# makey_makey.net
KiCad netlist of a schematic drawn in EAGLE
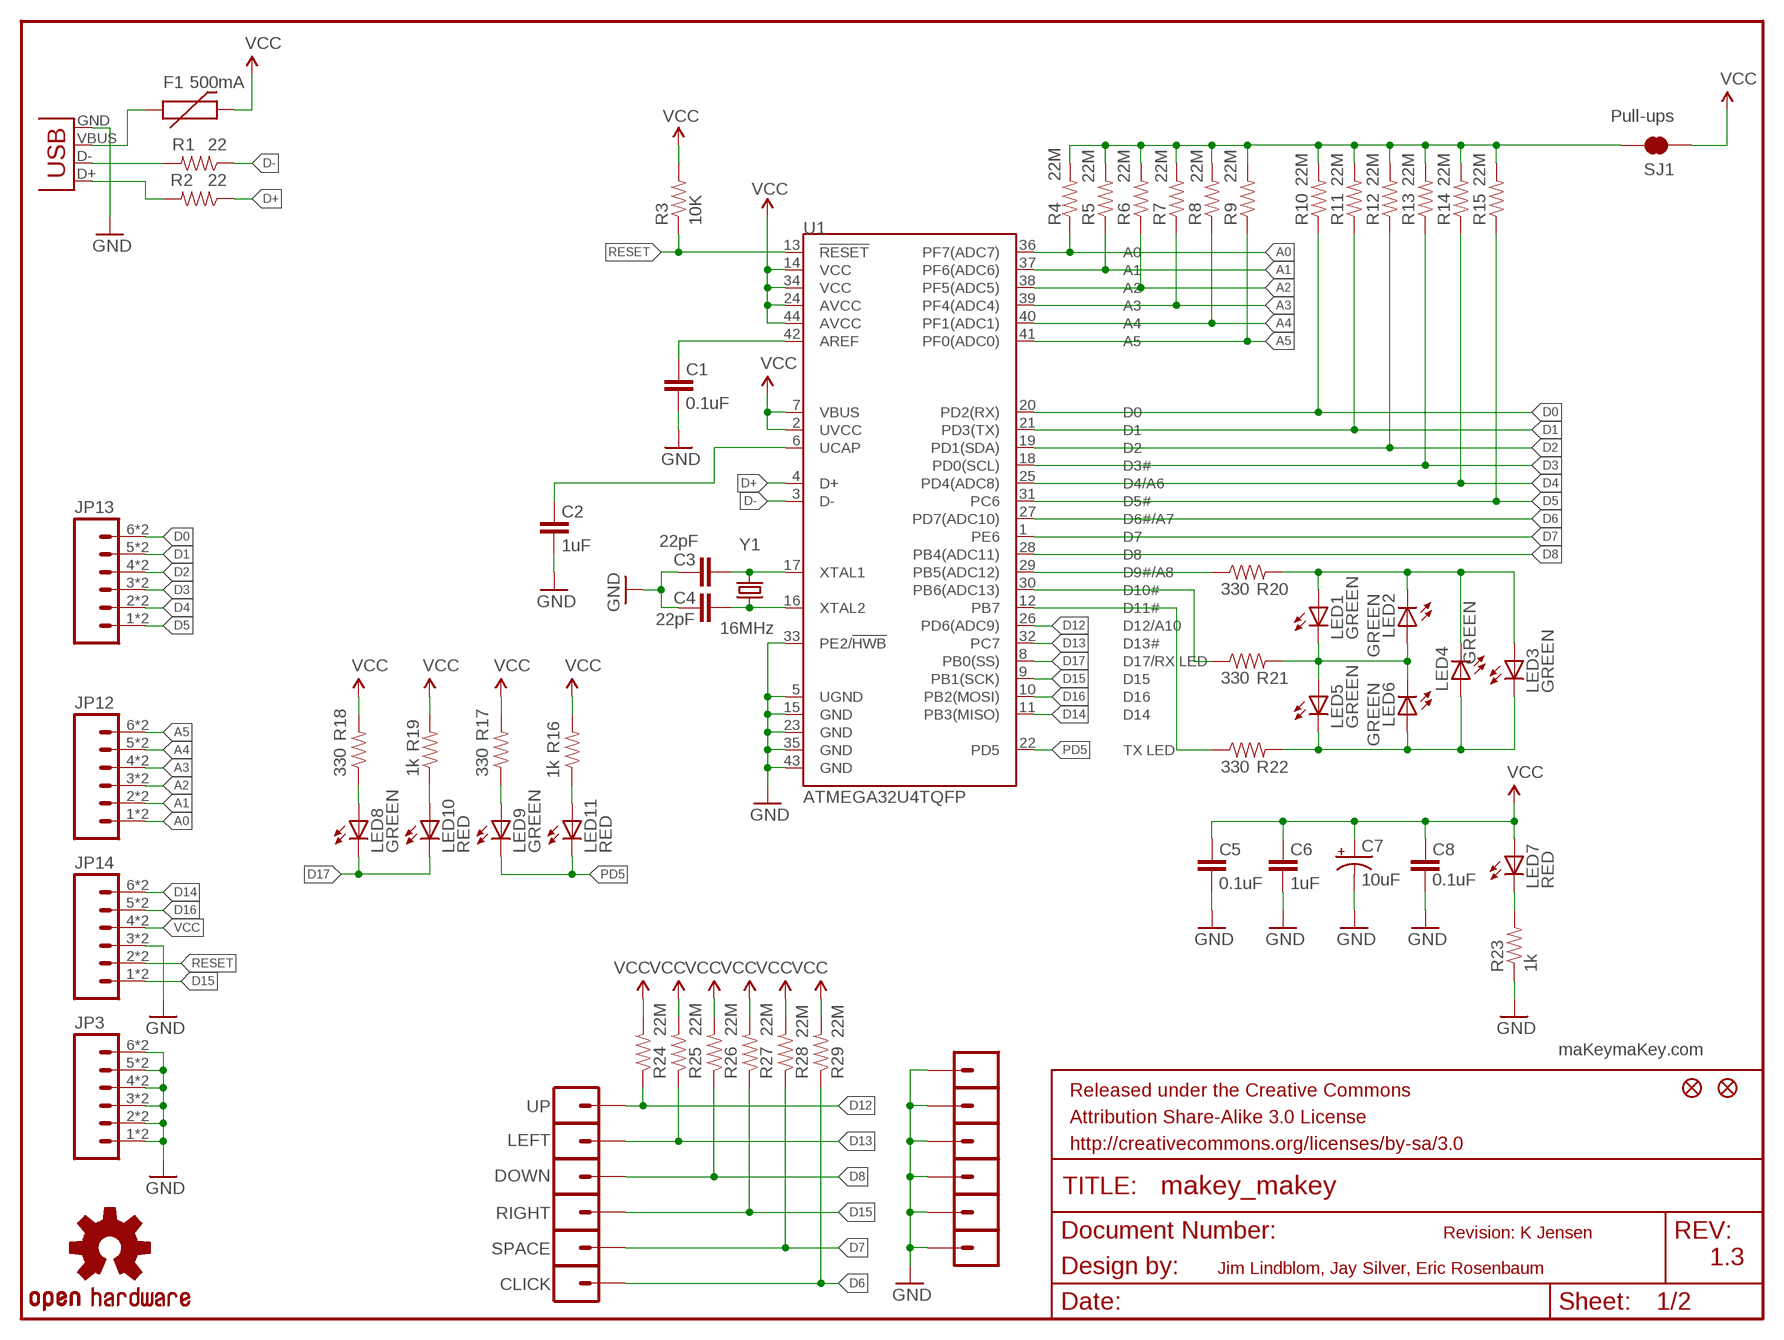
[diagram p0: schematic, sheet 1]
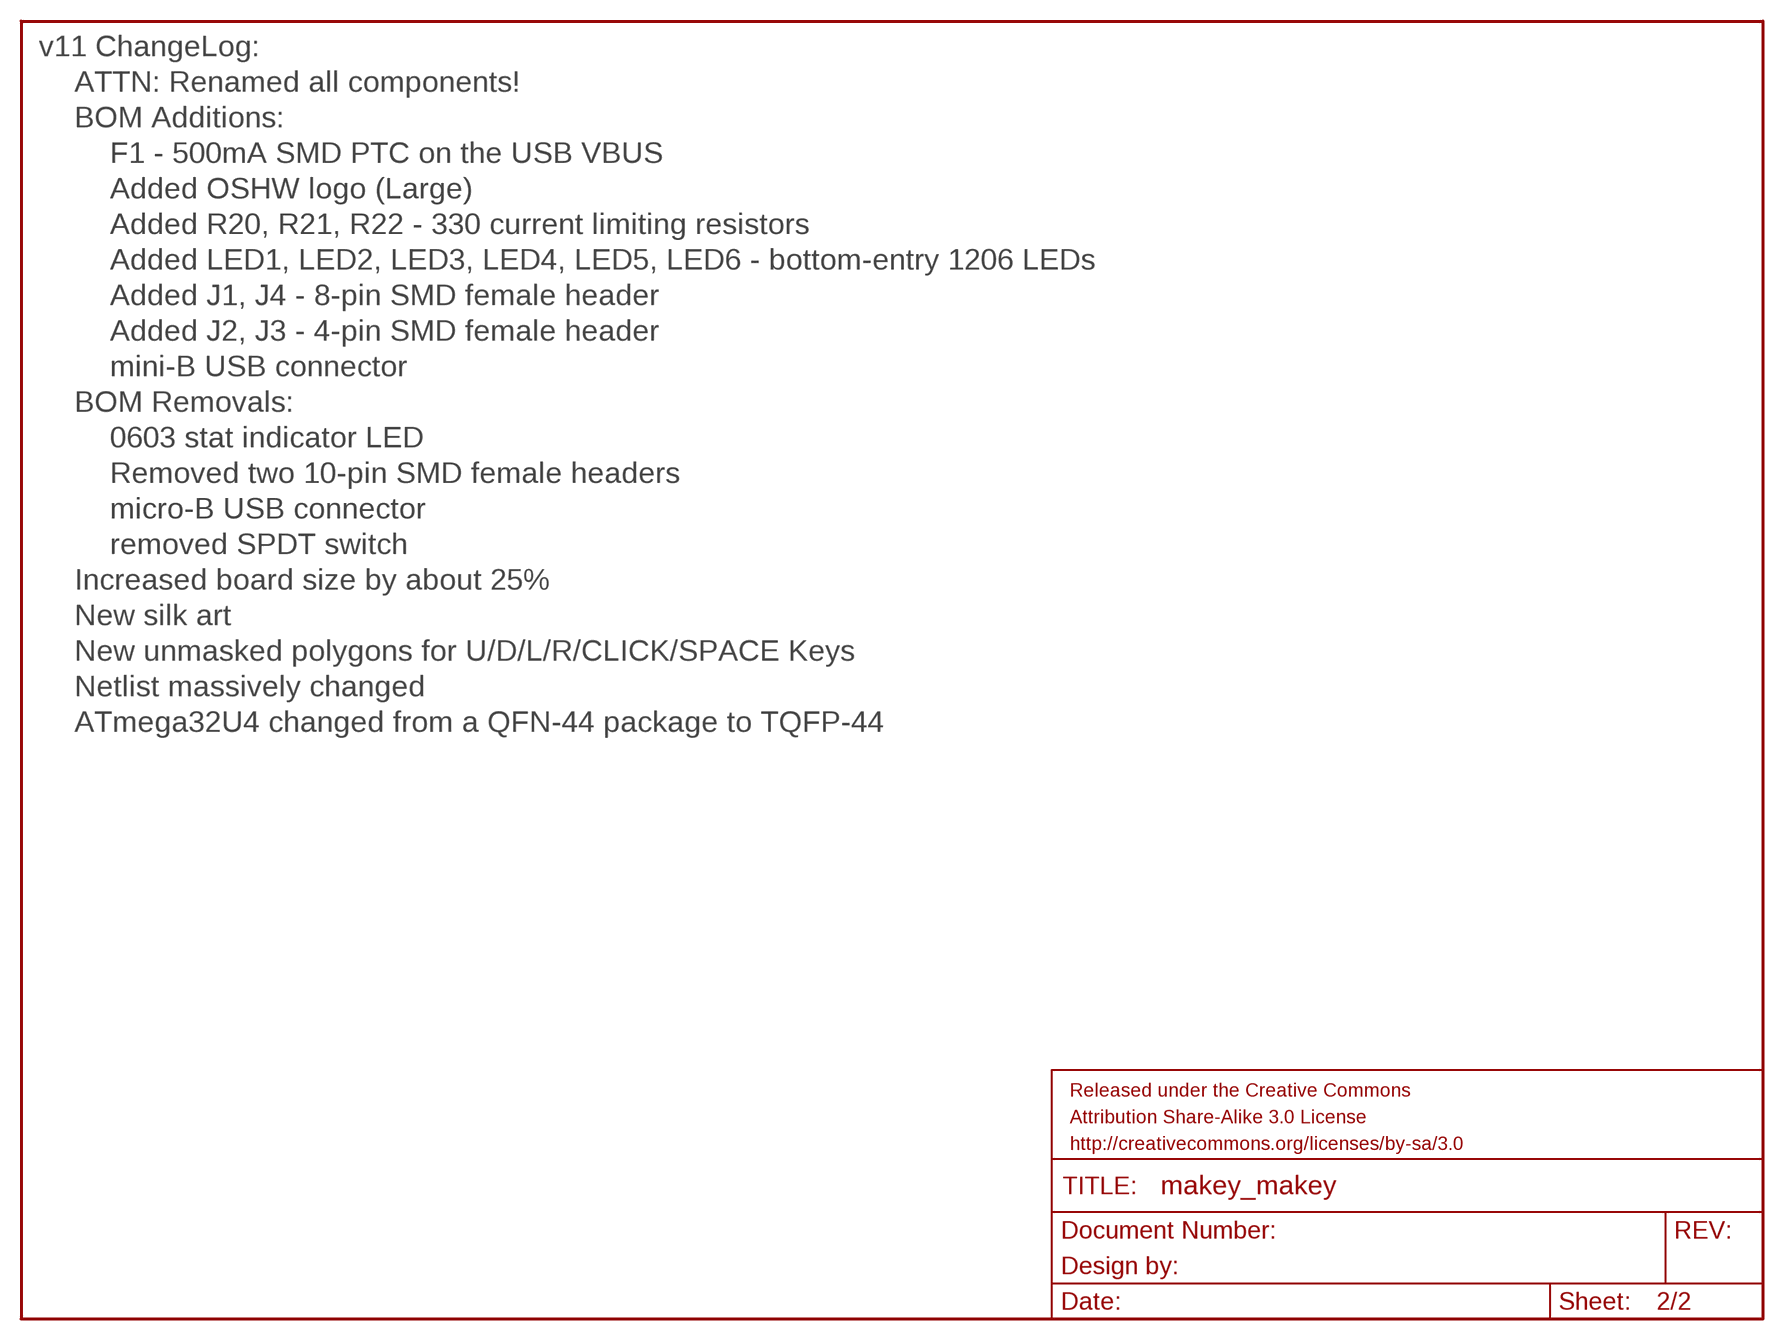
[diagram p1: schematic, sheet 2]

(export (version "E")
  (design (tool "Eeschema 10.0.6"))
  (components
    (comp (ref "C1")
      (value "0.1uF")
      (footprint "eagle-import:0603-CAP")
      (libsource (lib "eagle-import") (part "CAP0603-CAP"))
    )
    (comp (ref "C2")
      (value "1uF")
      (footprint "eagle-import:0603-CAP")
      (libsource (lib "eagle-import") (part "CAP0603-CAP"))
    )
    (comp (ref "C3")
      (value "22pF")
      (footprint "eagle-import:0603-CAP")
      (libsource (lib "eagle-import") (part "CAP0603-CAP"))
    )
    (comp (ref "C4")
      (value "22pF")
      (footprint "eagle-import:0603-CAP")
      (libsource (lib "eagle-import") (part "CAP0603-CAP"))
    )
    (comp (ref "C5")
      (value "0.1uF")
      (footprint "eagle-import:0603-CAP")
      (libsource (lib "eagle-import") (part "CAP0603-CAP"))
    )
    (comp (ref "C6")
      (value "1uF")
      (footprint "eagle-import:0603-CAP")
      (libsource (lib "eagle-import") (part "CAP0603-CAP"))
    )
    (comp (ref "C7")
      (value "10uF")
      (footprint "eagle-import:EIA3216")
      (libsource (lib "eagle-import") (part "CAP_POL1206"))
    )
    (comp (ref "C8")
      (value "0.1uF")
      (footprint "eagle-import:0603-CAP")
      (libsource (lib "eagle-import") (part "CAP0603-CAP"))
    )
    (comp (ref "CLICK")
      (value "M01ALLIGATOR-3MM")
      (footprint "eagle-import:1X01_ALLIGATOR_3MM")
      (libsource (lib "eagle-import") (part "M01ALLIGATOR-3MM"))
    )
    (comp (ref "DOWN")
      (value "M01ALLIGATOR-3MM")
      (footprint "eagle-import:1X01_ALLIGATOR_3MM")
      (libsource (lib "eagle-import") (part "M01ALLIGATOR-3MM"))
    )
    (comp (ref "F1")
      (value "500mA")
      (footprint "eagle-import:PTC-1206-WIDE")
      (libsource (lib "eagle-import") (part "PTCSMD-W"))
    )
    (comp (ref "JP1")
      (value "FIDUCIALUFIDUCIAL")
      (footprint "eagle-import:MICRO-FIDUCIAL")
      (libsource (lib "eagle-import") (part "FIDUCIALUFIDUCIAL"))
    )
    (comp (ref "JP2")
      (value "FIDUCIALUFIDUCIAL")
      (footprint "eagle-import:MICRO-FIDUCIAL")
      (libsource (lib "eagle-import") (part "FIDUCIALUFIDUCIAL"))
    )
    (comp (ref "JP3")
      (value "M06SMD-STRAIGHT-COMBO")
      (footprint "eagle-import:1X06_SMD_STRAIGHT_COMBO")
      (libsource (lib "eagle-import") (part "M06SMD-STRAIGHT-COMBO"))
    )
    (comp (ref "JP5")
      (value "M01ALLIGATOR-3MM")
      (footprint "eagle-import:1X01_ALLIGATOR_3MM")
      (libsource (lib "eagle-import") (part "M01ALLIGATOR-3MM"))
    )
    (comp (ref "JP6")
      (value "M01ALLIGATOR-3MM")
      (footprint "eagle-import:1X01_ALLIGATOR_3MM")
      (libsource (lib "eagle-import") (part "M01ALLIGATOR-3MM"))
    )
    (comp (ref "JP7")
      (value "M01ALLIGATOR-3MM")
      (footprint "eagle-import:1X01_ALLIGATOR_3MM")
      (libsource (lib "eagle-import") (part "M01ALLIGATOR-3MM"))
    )
    (comp (ref "JP8")
      (value "M01ALLIGATOR-3MM")
      (footprint "eagle-import:1X01_ALLIGATOR_3MM")
      (libsource (lib "eagle-import") (part "M01ALLIGATOR-3MM"))
    )
    (comp (ref "JP10")
      (value "M01ALLIGATOR-3MM")
      (footprint "eagle-import:1X01_ALLIGATOR_3MM")
      (libsource (lib "eagle-import") (part "M01ALLIGATOR-3MM"))
    )
    (comp (ref "JP11")
      (value "M01ALLIGATOR-3MM")
      (footprint "eagle-import:1X01_ALLIGATOR_3MM")
      (libsource (lib "eagle-import") (part "M01ALLIGATOR-3MM"))
    )
    (comp (ref "JP12")
      (value "M06SMD-STRAIGHT-COMBO")
      (footprint "eagle-import:1X06_SMD_STRAIGHT_COMBO")
      (libsource (lib "eagle-import") (part "M06SMD-STRAIGHT-COMBO"))
    )
    (comp (ref "JP13")
      (value "M06SMD-STRAIGHT-COMBO")
      (footprint "eagle-import:1X06_SMD_STRAIGHT_COMBO")
      (libsource (lib "eagle-import") (part "M06SMD-STRAIGHT-COMBO"))
    )
    (comp (ref "JP14")
      (value "M06SMD-STRAIGHT-COMBO")
      (footprint "eagle-import:1X06_SMD_STRAIGHT_COMBO")
      (libsource (lib "eagle-import") (part "M06SMD-STRAIGHT-COMBO"))
    )
    (comp (ref "LED1")
      (value "GREEN")
      (footprint "eagle-import:LED-1206-BOTTOM")
      (libsource (lib "eagle-import") (part "LED1206-BOTTOM"))
    )
    (comp (ref "LED2")
      (value "GREEN")
      (footprint "eagle-import:LED-1206-BOTTOM")
      (libsource (lib "eagle-import") (part "LED1206-BOTTOM"))
    )
    (comp (ref "LED3")
      (value "GREEN")
      (footprint "eagle-import:LED-1206-BOTTOM")
      (libsource (lib "eagle-import") (part "LED1206-BOTTOM"))
    )
    (comp (ref "LED4")
      (value "GREEN")
      (footprint "eagle-import:LED-1206-BOTTOM")
      (libsource (lib "eagle-import") (part "LED1206-BOTTOM"))
    )
    (comp (ref "LED5")
      (value "GREEN")
      (footprint "eagle-import:LED-1206-BOTTOM")
      (libsource (lib "eagle-import") (part "LED1206-BOTTOM"))
    )
    (comp (ref "LED6")
      (value "GREEN")
      (footprint "eagle-import:LED-1206-BOTTOM")
      (libsource (lib "eagle-import") (part "LED1206-BOTTOM"))
    )
    (comp (ref "LED7")
      (value "RED")
      (footprint "eagle-import:LED-0603")
      (libsource (lib "eagle-import") (part "LED0603"))
    )
    (comp (ref "LED8")
      (value "GREEN")
      (footprint "eagle-import:LED-0603")
      (libsource (lib "eagle-import") (part "SparkFun-LED_LED0603"))
    )
    (comp (ref "LED9")
      (value "GREEN")
      (footprint "eagle-import:LED-0603")
      (libsource (lib "eagle-import") (part "SparkFun-LED_LED0603"))
    )
    (comp (ref "LED10")
      (value "RED")
      (footprint "eagle-import:LED-0603")
      (libsource (lib "eagle-import") (part "SparkFun-LED_LED0603"))
    )
    (comp (ref "LED11")
      (value "RED")
      (footprint "eagle-import:LED-0603")
      (libsource (lib "eagle-import") (part "SparkFun-LED_LED0603"))
    )
    (comp (ref "LEFT")
      (value "M01ALLIGATOR-3MM")
      (footprint "eagle-import:1X01_ALLIGATOR_3MM")
      (libsource (lib "eagle-import") (part "M01ALLIGATOR-3MM"))
    )
    (comp (ref "R1")
      (value "22")
      (footprint "eagle-import:0603-RES")
      (libsource (lib "eagle-import") (part "RESISTOR0603-RES"))
    )
    (comp (ref "R2")
      (value "22")
      (footprint "eagle-import:0603-RES")
      (libsource (lib "eagle-import") (part "RESISTOR0603-RES"))
    )
    (comp (ref "R3")
      (value "10K")
      (footprint "eagle-import:0603-RES")
      (libsource (lib "eagle-import") (part "RESISTOR0603-RES"))
    )
    (comp (ref "R4")
      (value "22M")
      (footprint "eagle-import:0603-RES")
      (libsource (lib "eagle-import") (part "RESISTOR0603-RES"))
    )
    (comp (ref "R5")
      (value "22M")
      (footprint "eagle-import:0603-RES")
      (libsource (lib "eagle-import") (part "RESISTOR0603-RES"))
    )
    (comp (ref "R6")
      (value "22M")
      (footprint "eagle-import:0603-RES")
      (libsource (lib "eagle-import") (part "RESISTOR0603-RES"))
    )
    (comp (ref "R7")
      (value "22M")
      (footprint "eagle-import:0603-RES")
      (libsource (lib "eagle-import") (part "RESISTOR0603-RES"))
    )
    (comp (ref "R8")
      (value "22M")
      (footprint "eagle-import:0603-RES")
      (libsource (lib "eagle-import") (part "RESISTOR0603-RES"))
    )
    (comp (ref "R9")
      (value "22M")
      (footprint "eagle-import:0603-RES")
      (libsource (lib "eagle-import") (part "RESISTOR0603-RES"))
    )
    (comp (ref "R10")
      (value "22M")
      (footprint "eagle-import:0603-RES")
      (libsource (lib "eagle-import") (part "RESISTOR0603-RES"))
    )
    (comp (ref "R11")
      (value "22M")
      (footprint "eagle-import:0603-RES")
      (libsource (lib "eagle-import") (part "RESISTOR0603-RES"))
    )
    (comp (ref "R12")
      (value "22M")
      (footprint "eagle-import:0603-RES")
      (libsource (lib "eagle-import") (part "RESISTOR0603-RES"))
    )
    (comp (ref "R13")
      (value "22M")
      (footprint "eagle-import:0603-RES")
      (libsource (lib "eagle-import") (part "RESISTOR0603-RES"))
    )
    (comp (ref "R14")
      (value "22M")
      (footprint "eagle-import:0603-RES")
      (libsource (lib "eagle-import") (part "RESISTOR0603-RES"))
    )
    (comp (ref "R15")
      (value "22M")
      (footprint "eagle-import:0603-RES")
      (libsource (lib "eagle-import") (part "RESISTOR0603-RES"))
    )
    (comp (ref "R16")
      (value "1k")
      (footprint "eagle-import:0603-RES")
      (libsource (lib "eagle-import") (part "SparkFun-Passives_RESISTOR0603-RES"))
    )
    (comp (ref "R17")
      (value "330")
      (footprint "eagle-import:0603-RES")
      (libsource (lib "eagle-import") (part "SparkFun-Passives_RESISTOR0603-RES"))
    )
    (comp (ref "R18")
      (value "330")
      (footprint "eagle-import:0603-RES")
      (libsource (lib "eagle-import") (part "SparkFun-Passives_RESISTOR0603-RES"))
    )
    (comp (ref "R19")
      (value "1k")
      (footprint "eagle-import:0603-RES")
      (libsource (lib "eagle-import") (part "SparkFun-Passives_RESISTOR0603-RES"))
    )
    (comp (ref "R20")
      (value "330")
      (footprint "eagle-import:0603-RES")
      (libsource (lib "eagle-import") (part "SparkFun-Passives_RESISTOR0603-RES"))
    )
    (comp (ref "R21")
      (value "330")
      (footprint "eagle-import:0603-RES")
      (libsource (lib "eagle-import") (part "SparkFun-Passives_RESISTOR0603-RES"))
    )
    (comp (ref "R22")
      (value "330")
      (footprint "eagle-import:0603-RES")
      (libsource (lib "eagle-import") (part "SparkFun-Passives_RESISTOR0603-RES"))
    )
    (comp (ref "R23")
      (value "1k")
      (footprint "eagle-import:0603-RES")
      (libsource (lib "eagle-import") (part "RESISTOR0603-RES"))
    )
    (comp (ref "R24")
      (value "22M")
      (footprint "eagle-import:0603-RES")
      (libsource (lib "eagle-import") (part "RESISTOR0603-RES"))
    )
    (comp (ref "R25")
      (value "22M")
      (footprint "eagle-import:0603-RES")
      (libsource (lib "eagle-import") (part "RESISTOR0603-RES"))
    )
    (comp (ref "R26")
      (value "22M")
      (footprint "eagle-import:0603-RES")
      (libsource (lib "eagle-import") (part "RESISTOR0603-RES"))
    )
    (comp (ref "R27")
      (value "22M")
      (footprint "eagle-import:0603-RES")
      (libsource (lib "eagle-import") (part "RESISTOR0603-RES"))
    )
    (comp (ref "R28")
      (value "22M")
      (footprint "eagle-import:0603-RES")
      (libsource (lib "eagle-import") (part "RESISTOR0603-RES"))
    )
    (comp (ref "R29")
      (value "22M")
      (footprint "eagle-import:0603-RES")
      (libsource (lib "eagle-import") (part "RESISTOR0603-RES"))
    )
    (comp (ref "RIGHT")
      (value "M01ALLIGATOR-3MM")
      (footprint "eagle-import:1X01_ALLIGATOR_3MM")
      (libsource (lib "eagle-import") (part "M01ALLIGATOR-3MM"))
    )
    (comp (ref "SJ1")
      (value "Pull-ups")
      (footprint "eagle-import:SJ_2S-TRACE")
      (libsource (lib "eagle-import") (part "SOLDERJUMPER-OLDTRACE"))
    )
    (comp (ref "SPACE")
      (value "M01ALLIGATOR-3MM")
      (footprint "eagle-import:1X01_ALLIGATOR_3MM")
      (libsource (lib "eagle-import") (part "M01ALLIGATOR-3MM"))
    )
    (comp (ref "U$1")
      (value "OSHW-LOGOM")
      (footprint "eagle-import:OSHW-LOGO-M")
      (libsource (lib "eagle-import") (part "OSHW-LOGOM"))
    )
    (comp (ref "U1")
      (value "ATMEGA32U4TQFP")
      (footprint "eagle-import:TQFP44")
      (libsource (lib "eagle-import") (part "ATMEGA32U4TQFP"))
    )
    (comp (ref "UP")
      (value "M01ALLIGATOR-3MM")
      (footprint "eagle-import:1X01_ALLIGATOR_3MM")
      (libsource (lib "eagle-import") (part "M01ALLIGATOR-3MM"))
    )
    (comp (ref "X1")
      (value "USBSMD")
      (footprint "eagle-import:USB-MINIB")
      (libsource (lib "eagle-import") (part "USBSMD"))
    )
    (comp (ref "Y1")
      (value "16MHz")
      (footprint "eagle-import:CRYSTAL-SMD-5X3")
      (libsource (lib "eagle-import") (part "CRYSTAL5X3"))
    )
  )
  (nets
    (net (code "1") (name "A0") (class "Default")
      (node (ref "JP12") (pin "1") (pinfunction "1_1") (pintype "passive"))
      (node (ref "JP12") (pin "1-2") (pinfunction "1_1-2") (pintype "passive"))
      (node (ref "R4") (pin "1") (pinfunction "1_1") (pintype "passive"))
      (node (ref "U1") (pin "36") (pinfunction "PF7(ADC7)_36") (pintype "bidirectional"))
    )
    (net (code "2") (name "A1") (class "Default")
      (node (ref "JP12") (pin "2") (pinfunction "2_2") (pintype "passive"))
      (node (ref "JP12") (pin "2-2") (pinfunction "2_2-2") (pintype "passive"))
      (node (ref "R5") (pin "1") (pinfunction "1_1") (pintype "passive"))
      (node (ref "U1") (pin "37") (pinfunction "PF6(ADC6)_37") (pintype "bidirectional"))
    )
    (net (code "3") (name "A2") (class "Default")
      (node (ref "JP12") (pin "3") (pinfunction "3_3") (pintype "passive"))
      (node (ref "JP12") (pin "3-2") (pinfunction "3_3-2") (pintype "passive"))
      (node (ref "R6") (pin "1") (pinfunction "1_1") (pintype "passive"))
      (node (ref "U1") (pin "38") (pinfunction "PF5(ADC5)_38") (pintype "bidirectional"))
    )
    (net (code "4") (name "A3") (class "Default")
      (node (ref "JP12") (pin "4") (pinfunction "4_4") (pintype "passive"))
      (node (ref "JP12") (pin "4-2") (pinfunction "4_4-2") (pintype "passive"))
      (node (ref "R7") (pin "1") (pinfunction "1_1") (pintype "passive"))
      (node (ref "U1") (pin "39") (pinfunction "PF4(ADC4)_39") (pintype "bidirectional"))
    )
    (net (code "5") (name "A4") (class "Default")
      (node (ref "JP12") (pin "5") (pinfunction "5_5") (pintype "passive"))
      (node (ref "JP12") (pin "5-2") (pinfunction "5_5-2") (pintype "passive"))
      (node (ref "R8") (pin "1") (pinfunction "1_1") (pintype "passive"))
      (node (ref "U1") (pin "40") (pinfunction "PF1(ADC1)_40") (pintype "bidirectional"))
    )
    (net (code "6") (name "A5") (class "Default")
      (node (ref "JP12") (pin "6") (pinfunction "6_6") (pintype "passive"))
      (node (ref "JP12") (pin "6-2") (pinfunction "6_6-2") (pintype "passive"))
      (node (ref "R9") (pin "1") (pinfunction "1_1") (pintype "passive"))
      (node (ref "U1") (pin "41") (pinfunction "PF0(ADC0)_41") (pintype "bidirectional"))
    )
    (net (code "7") (name "D+") (class "Default")
      (node (ref "R2") (pin "1") (pinfunction "1_1") (pintype "passive"))
      (node (ref "U1") (pin "4") (pinfunction "D+_4") (pintype "bidirectional"))
    )
    (net (code "8") (name "D-") (class "Default")
      (node (ref "R1") (pin "1") (pinfunction "1_1") (pintype "passive"))
      (node (ref "U1") (pin "3") (pinfunction "D-_3") (pintype "bidirectional"))
    )
    (net (code "9") (name "D0") (class "Default")
      (node (ref "JP13") (pin "6") (pinfunction "6_6") (pintype "passive"))
      (node (ref "JP13") (pin "6-2") (pinfunction "6_6-2") (pintype "passive"))
      (node (ref "R10") (pin "1") (pinfunction "1_1") (pintype "passive"))
      (node (ref "U1") (pin "20") (pinfunction "PD2(RX)_20") (pintype "bidirectional"))
    )
    (net (code "10") (name "D1") (class "Default")
      (node (ref "JP13") (pin "5") (pinfunction "5_5") (pintype "passive"))
      (node (ref "JP13") (pin "5-2") (pinfunction "5_5-2") (pintype "passive"))
      (node (ref "R11") (pin "1") (pinfunction "1_1") (pintype "passive"))
      (node (ref "U1") (pin "21") (pinfunction "PD3(TX)_21") (pintype "bidirectional"))
    )
    (net (code "11") (name "D2") (class "Default")
      (node (ref "JP13") (pin "4") (pinfunction "4_4") (pintype "passive"))
      (node (ref "JP13") (pin "4-2") (pinfunction "4_4-2") (pintype "passive"))
      (node (ref "R12") (pin "1") (pinfunction "1_1") (pintype "passive"))
      (node (ref "U1") (pin "19") (pinfunction "PD1(SDA)_19") (pintype "bidirectional"))
    )
    (net (code "12") (name "D3") (class "Default")
      (node (ref "JP13") (pin "3") (pinfunction "3_3") (pintype "passive"))
      (node (ref "JP13") (pin "3-2") (pinfunction "3_3-2") (pintype "passive"))
      (node (ref "R13") (pin "1") (pinfunction "1_1") (pintype "passive"))
      (node (ref "U1") (pin "18") (pinfunction "PD0(SCL)_18") (pintype "bidirectional"))
    )
    (net (code "13") (name "D4") (class "Default")
      (node (ref "JP13") (pin "2") (pinfunction "2_2") (pintype "passive"))
      (node (ref "JP13") (pin "2-2") (pinfunction "2_2-2") (pintype "passive"))
      (node (ref "R14") (pin "1") (pinfunction "1_1") (pintype "passive"))
      (node (ref "U1") (pin "25") (pinfunction "PD4(ADC8)_25") (pintype "bidirectional"))
    )
    (net (code "14") (name "D5") (class "Default")
      (node (ref "JP13") (pin "1") (pinfunction "1_1") (pintype "passive"))
      (node (ref "JP13") (pin "1-2") (pinfunction "1_1-2") (pintype "passive"))
      (node (ref "R15") (pin "1") (pinfunction "1_1") (pintype "passive"))
      (node (ref "U1") (pin "31") (pinfunction "PC6_31") (pintype "bidirectional"))
    )
    (net (code "15") (name "D6") (class "Default")
      (node (ref "CLICK") (pin "1@0") (pinfunction "1_1@0") (pintype "passive"))
      (node (ref "CLICK") (pin "1@2") (pinfunction "1_1@2") (pintype "passive"))
      (node (ref "R29") (pin "1") (pinfunction "1_1") (pintype "passive"))
      (node (ref "U1") (pin "27") (pinfunction "PD7(ADC10)_27") (pintype "bidirectional"))
    )
    (net (code "16") (name "D7") (class "Default")
      (node (ref "R28") (pin "1") (pinfunction "1_1") (pintype "passive"))
      (node (ref "SPACE") (pin "1@0") (pinfunction "1_1@0") (pintype "passive"))
      (node (ref "SPACE") (pin "1@2") (pinfunction "1_1@2") (pintype "passive"))
      (node (ref "U1") (pin "1") (pinfunction "PE6_1") (pintype "bidirectional"))
    )
    (net (code "17") (name "D8") (class "Default")
      (node (ref "DOWN") (pin "1@0") (pinfunction "1_1@0") (pintype "passive"))
      (node (ref "DOWN") (pin "1@2") (pinfunction "1_1@2") (pintype "passive"))
      (node (ref "R26") (pin "1") (pinfunction "1_1") (pintype "passive"))
      (node (ref "U1") (pin "28") (pinfunction "PB4(ADC11)_28") (pintype "bidirectional"))
    )
    (net (code "18") (name "D12") (class "Default")
      (node (ref "R24") (pin "1") (pinfunction "1_1") (pintype "passive"))
      (node (ref "U1") (pin "26") (pinfunction "PD6(ADC9)_26") (pintype "bidirectional"))
      (node (ref "UP") (pin "1@0") (pinfunction "1_1@0") (pintype "passive"))
      (node (ref "UP") (pin "1@2") (pinfunction "1_1@2") (pintype "passive"))
    )
    (net (code "19") (name "D13") (class "Default")
      (node (ref "LEFT") (pin "1@0") (pinfunction "1_1@0") (pintype "passive"))
      (node (ref "LEFT") (pin "1@2") (pinfunction "1_1@2") (pintype "passive"))
      (node (ref "R25") (pin "1") (pinfunction "1_1") (pintype "passive"))
      (node (ref "U1") (pin "32") (pinfunction "PC7_32") (pintype "bidirectional"))
    )
    (net (code "20") (name "D14") (class "Default")
      (node (ref "JP14") (pin "6") (pinfunction "6_6") (pintype "passive"))
      (node (ref "JP14") (pin "6-2") (pinfunction "6_6-2") (pintype "passive"))
      (node (ref "U1") (pin "11") (pinfunction "PB3(MISO)_11") (pintype "bidirectional"))
    )
    (net (code "21") (name "D15") (class "Default")
      (node (ref "JP14") (pin "1") (pinfunction "1_1") (pintype "passive"))
      (node (ref "JP14") (pin "1-2") (pinfunction "1_1-2") (pintype "passive"))
      (node (ref "R27") (pin "1") (pinfunction "1_1") (pintype "passive"))
      (node (ref "RIGHT") (pin "1@0") (pinfunction "1_1@0") (pintype "passive"))
      (node (ref "RIGHT") (pin "1@2") (pinfunction "1_1@2") (pintype "passive"))
      (node (ref "U1") (pin "9") (pinfunction "PB1(SCK)_9") (pintype "bidirectional"))
    )
    (net (code "22") (name "D16") (class "Default")
      (node (ref "JP14") (pin "5") (pinfunction "5_5") (pintype "passive"))
      (node (ref "JP14") (pin "5-2") (pinfunction "5_5-2") (pintype "passive"))
      (node (ref "U1") (pin "10") (pinfunction "PB2(MOSI)_10") (pintype "bidirectional"))
    )
    (net (code "23") (name "D17") (class "Default")
      (node (ref "LED10") (pin "C") (pinfunction "C_C") (pintype "passive"))
      (node (ref "LED8") (pin "C") (pinfunction "C_C") (pintype "passive"))
      (node (ref "U1") (pin "8") (pinfunction "PB0(SS)_8") (pintype "bidirectional"))
    )
    (net (code "24") (name "GND") (class "Default")
      (node (ref "C1") (pin "1") (pinfunction "1_1") (pintype "passive"))
      (node (ref "C2") (pin "1") (pinfunction "1_1") (pintype "passive"))
      (node (ref "C3") (pin "2") (pinfunction "2_2") (pintype "passive"))
      (node (ref "C4") (pin "2") (pinfunction "2_2") (pintype "passive"))
      (node (ref "C5") (pin "1") (pinfunction "1_1") (pintype "passive"))
      (node (ref "C6") (pin "1") (pinfunction "1_1") (pintype "passive"))
      (node (ref "C7") (pin "C") (pinfunction "-_C") (pintype "passive"))
      (node (ref "C8") (pin "1") (pinfunction "1_1") (pintype "passive"))
      (node (ref "JP10") (pin "1@0") (pinfunction "1_1@0") (pintype "passive"))
      (node (ref "JP10") (pin "1@2") (pinfunction "1_1@2") (pintype "passive"))
      (node (ref "JP11") (pin "1@0") (pinfunction "1_1@0") (pintype "passive"))
      (node (ref "JP11") (pin "1@2") (pinfunction "1_1@2") (pintype "passive"))
      (node (ref "JP14") (pin "3") (pinfunction "3_3") (pintype "passive"))
      (node (ref "JP14") (pin "3-2") (pinfunction "3_3-2") (pintype "passive"))
      (node (ref "JP3") (pin "1") (pinfunction "1_1") (pintype "passive"))
      (node (ref "JP3") (pin "1-2") (pinfunction "1_1-2") (pintype "passive"))
      (node (ref "JP3") (pin "2") (pinfunction "2_2") (pintype "passive"))
      (node (ref "JP3") (pin "2-2") (pinfunction "2_2-2") (pintype "passive"))
      (node (ref "JP3") (pin "3") (pinfunction "3_3") (pintype "passive"))
      (node (ref "JP3") (pin "3-2") (pinfunction "3_3-2") (pintype "passive"))
      (node (ref "JP3") (pin "4") (pinfunction "4_4") (pintype "passive"))
      (node (ref "JP3") (pin "4-2") (pinfunction "4_4-2") (pintype "passive"))
      (node (ref "JP3") (pin "5") (pinfunction "5_5") (pintype "passive"))
      (node (ref "JP3") (pin "5-2") (pinfunction "5_5-2") (pintype "passive"))
      (node (ref "JP3") (pin "6") (pinfunction "6_6") (pintype "passive"))
      (node (ref "JP3") (pin "6-2") (pinfunction "6_6-2") (pintype "passive"))
      (node (ref "JP5") (pin "1@0") (pinfunction "1_1@0") (pintype "passive"))
      (node (ref "JP5") (pin "1@2") (pinfunction "1_1@2") (pintype "passive"))
      (node (ref "JP6") (pin "1@0") (pinfunction "1_1@0") (pintype "passive"))
      (node (ref "JP6") (pin "1@2") (pinfunction "1_1@2") (pintype "passive"))
      (node (ref "JP7") (pin "1@0") (pinfunction "1_1@0") (pintype "passive"))
      (node (ref "JP7") (pin "1@2") (pinfunction "1_1@2") (pintype "passive"))
      (node (ref "JP8") (pin "1@0") (pinfunction "1_1@0") (pintype "passive"))
      (node (ref "JP8") (pin "1@2") (pinfunction "1_1@2") (pintype "passive"))
      (node (ref "R23") (pin "1") (pinfunction "1_1") (pintype "passive"))
      (node (ref "U1") (pin "15") (pinfunction "GND_15") (pintype "bidirectional"))
      (node (ref "U1") (pin "23") (pinfunction "GND_23") (pintype "bidirectional"))
      (node (ref "U1") (pin "33") (pinfunction "PE2/~{HWB}_33") (pintype "bidirectional"))
      (node (ref "U1") (pin "35") (pinfunction "GND_35") (pintype "bidirectional"))
      (node (ref "U1") (pin "43") (pinfunction "GND_43") (pintype "bidirectional"))
      (node (ref "U1") (pin "5") (pinfunction "UGND_5") (pintype "bidirectional"))
      (node (ref "X1") (pin "GND") (pinfunction "GND_GND") (pintype "bidirectional"))
    )
    (net (code "25") (name "Net-(F1-Pad1)") (class "Default")
      (node (ref "F1") (pin "1") (pinfunction "1_1") (pintype "bidirectional"))
      (node (ref "X1") (pin "VBUS") (pinfunction "VBUS_VBUS") (pintype "bidirectional"))
    )
    (net (code "26") (name "Net-(LED1-PadA)") (class "Default")
      (node (ref "LED1") (pin "A") (pinfunction "A_A") (pintype "passive"))
      (node (ref "LED2") (pin "C") (pinfunction "C_C") (pintype "passive"))
      (node (ref "LED3") (pin "A") (pinfunction "A_A") (pintype "passive"))
      (node (ref "LED4") (pin "C") (pinfunction "C_C") (pintype "passive"))
      (node (ref "R20") (pin "2") (pinfunction "2_2") (pintype "passive"))
    )
    (net (code "27") (name "Net-(LED1-PadC)") (class "Default")
      (node (ref "LED1") (pin "C") (pinfunction "C_C") (pintype "passive"))
      (node (ref "LED2") (pin "A") (pinfunction "A_A") (pintype "passive"))
      (node (ref "LED5") (pin "A") (pinfunction "A_A") (pintype "passive"))
      (node (ref "LED6") (pin "C") (pinfunction "C_C") (pintype "passive"))
      (node (ref "R21") (pin "2") (pinfunction "2_2") (pintype "passive"))
    )
    (net (code "28") (name "Net-(LED3-PadC)") (class "Default")
      (node (ref "LED3") (pin "C") (pinfunction "C_C") (pintype "passive"))
      (node (ref "LED4") (pin "A") (pinfunction "A_A") (pintype "passive"))
      (node (ref "LED5") (pin "C") (pinfunction "C_C") (pintype "passive"))
      (node (ref "LED6") (pin "A") (pinfunction "A_A") (pintype "passive"))
      (node (ref "R22") (pin "2") (pinfunction "2_2") (pintype "passive"))
    )
    (net (code "29") (name "Net-(LED7-PadC)") (class "Default")
      (node (ref "LED7") (pin "C") (pinfunction "C_C") (pintype "passive"))
      (node (ref "R23") (pin "2") (pinfunction "2_2") (pintype "passive"))
    )
    (net (code "30") (name "Net-(LED8-PadA)") (class "Default")
      (node (ref "LED8") (pin "A") (pinfunction "A_A") (pintype "passive"))
      (node (ref "R18") (pin "1") (pinfunction "1_1") (pintype "passive"))
    )
    (net (code "31") (name "Net-(LED9-PadA)") (class "Default")
      (node (ref "LED9") (pin "A") (pinfunction "A_A") (pintype "passive"))
      (node (ref "R17") (pin "1") (pinfunction "1_1") (pintype "passive"))
    )
    (net (code "32") (name "Net-(LED10-PadA)") (class "Default")
      (node (ref "LED10") (pin "A") (pinfunction "A_A") (pintype "passive"))
      (node (ref "R19") (pin "1") (pinfunction "1_1") (pintype "passive"))
    )
    (net (code "33") (name "Net-(LED11-PadA)") (class "Default")
      (node (ref "LED11") (pin "A") (pinfunction "A_A") (pintype "passive"))
      (node (ref "R16") (pin "1") (pinfunction "1_1") (pintype "passive"))
    )
    (net (code "34") (name "Net-(R1-Pad2)") (class "Default")
      (node (ref "R1") (pin "2") (pinfunction "2_2") (pintype "passive"))
      (node (ref "X1") (pin "D-") (pinfunction "D-_D-") (pintype "bidirectional"))
    )
    (net (code "35") (name "Net-(R2-Pad2)") (class "Default")
      (node (ref "R2") (pin "2") (pinfunction "2_2") (pintype "passive"))
      (node (ref "X1") (pin "D+") (pinfunction "D+_D+") (pintype "bidirectional"))
    )
    (net (code "36") (name "Net-(R10-Pad2)") (class "Default")
      (node (ref "R10") (pin "2") (pinfunction "2_2") (pintype "passive"))
      (node (ref "R11") (pin "2") (pinfunction "2_2") (pintype "passive"))
      (node (ref "R12") (pin "2") (pinfunction "2_2") (pintype "passive"))
      (node (ref "R13") (pin "2") (pinfunction "2_2") (pintype "passive"))
      (node (ref "R14") (pin "2") (pinfunction "2_2") (pintype "passive"))
      (node (ref "R15") (pin "2") (pinfunction "2_2") (pintype "passive"))
      (node (ref "R4") (pin "2") (pinfunction "2_2") (pintype "passive"))
      (node (ref "R5") (pin "2") (pinfunction "2_2") (pintype "passive"))
      (node (ref "R6") (pin "2") (pinfunction "2_2") (pintype "passive"))
      (node (ref "R7") (pin "2") (pinfunction "2_2") (pintype "passive"))
      (node (ref "R8") (pin "2") (pinfunction "2_2") (pintype "passive"))
      (node (ref "R9") (pin "2") (pinfunction "2_2") (pintype "passive"))
      (node (ref "SJ1") (pin "2") (pinfunction "2_2") (pintype "passive"))
    )
    (net (code "37") (name "Net-(U1-AREF)") (class "Default")
      (node (ref "C1") (pin "2") (pinfunction "2_2") (pintype "passive"))
      (node (ref "U1") (pin "42") (pinfunction "AREF_42") (pintype "bidirectional"))
    )
    (net (code "38") (name "Net-(U1-PB5(ADC12))") (class "Default")
      (node (ref "R20") (pin "1") (pinfunction "1_1") (pintype "passive"))
      (node (ref "U1") (pin "29") (pinfunction "PB5(ADC12)_29") (pintype "bidirectional"))
    )
    (net (code "39") (name "Net-(U1-PB6(ADC13))") (class "Default")
      (node (ref "R21") (pin "1") (pinfunction "1_1") (pintype "passive"))
      (node (ref "U1") (pin "30") (pinfunction "PB6(ADC13)_30") (pintype "bidirectional"))
    )
    (net (code "40") (name "Net-(U1-PB7)") (class "Default")
      (node (ref "R22") (pin "1") (pinfunction "1_1") (pintype "passive"))
      (node (ref "U1") (pin "12") (pinfunction "PB7_12") (pintype "bidirectional"))
    )
    (net (code "41") (name "Net-(U1-UCAP)") (class "Default")
      (node (ref "C2") (pin "2") (pinfunction "2_2") (pintype "passive"))
      (node (ref "U1") (pin "6") (pinfunction "UCAP_6") (pintype "bidirectional"))
    )
    (net (code "42") (name "Net-(U1-XTAL1)") (class "Default")
      (node (ref "C3") (pin "1") (pinfunction "1_1") (pintype "passive"))
      (node (ref "U1") (pin "17") (pinfunction "XTAL1_17") (pintype "bidirectional"))
      (node (ref "Y1") (pin "3") (pinfunction "2_3") (pintype "passive"))
    )
    (net (code "43") (name "Net-(U1-XTAL2)") (class "Default")
      (node (ref "C4") (pin "1") (pinfunction "1_1") (pintype "passive"))
      (node (ref "U1") (pin "16") (pinfunction "XTAL2_16") (pintype "bidirectional"))
      (node (ref "Y1") (pin "1") (pinfunction "1_1") (pintype "passive"))
    )
    (net (code "44") (name "PD5") (class "Default")
      (node (ref "LED11") (pin "C") (pinfunction "C_C") (pintype "passive"))
      (node (ref "LED9") (pin "C") (pinfunction "C_C") (pintype "passive"))
      (node (ref "U1") (pin "22") (pinfunction "PD5_22") (pintype "bidirectional"))
    )
    (net (code "45") (name "RESET") (class "Default")
      (node (ref "JP14") (pin "2") (pinfunction "2_2") (pintype "passive"))
      (node (ref "JP14") (pin "2-2") (pinfunction "2_2-2") (pintype "passive"))
      (node (ref "R3") (pin "1") (pinfunction "1_1") (pintype "passive"))
      (node (ref "U1") (pin "13") (pinfunction "~{RESET}_13") (pintype "bidirectional"))
    )
    (net (code "46") (name "VCC") (class "Default")
      (node (ref "C5") (pin "2") (pinfunction "2_2") (pintype "passive"))
      (node (ref "C6") (pin "2") (pinfunction "2_2") (pintype "passive"))
      (node (ref "C7") (pin "A") (pinfunction "+_A") (pintype "passive"))
      (node (ref "C8") (pin "2") (pinfunction "2_2") (pintype "passive"))
      (node (ref "F1") (pin "2") (pinfunction "2_2") (pintype "bidirectional"))
      (node (ref "JP14") (pin "4") (pinfunction "4_4") (pintype "passive"))
      (node (ref "JP14") (pin "4-2") (pinfunction "4_4-2") (pintype "passive"))
      (node (ref "LED7") (pin "A") (pinfunction "A_A") (pintype "passive"))
      (node (ref "R16") (pin "2") (pinfunction "2_2") (pintype "passive"))
      (node (ref "R17") (pin "2") (pinfunction "2_2") (pintype "passive"))
      (node (ref "R18") (pin "2") (pinfunction "2_2") (pintype "passive"))
      (node (ref "R19") (pin "2") (pinfunction "2_2") (pintype "passive"))
      (node (ref "R24") (pin "2") (pinfunction "2_2") (pintype "passive"))
      (node (ref "R25") (pin "2") (pinfunction "2_2") (pintype "passive"))
      (node (ref "R26") (pin "2") (pinfunction "2_2") (pintype "passive"))
      (node (ref "R27") (pin "2") (pinfunction "2_2") (pintype "passive"))
      (node (ref "R28") (pin "2") (pinfunction "2_2") (pintype "passive"))
      (node (ref "R29") (pin "2") (pinfunction "2_2") (pintype "passive"))
      (node (ref "R3") (pin "2") (pinfunction "2_2") (pintype "passive"))
      (node (ref "SJ1") (pin "1") (pinfunction "1_1") (pintype "passive"))
      (node (ref "U1") (pin "14") (pinfunction "VCC_14") (pintype "bidirectional"))
      (node (ref "U1") (pin "2") (pinfunction "UVCC_2") (pintype "bidirectional"))
      (node (ref "U1") (pin "24") (pinfunction "AVCC_24") (pintype "bidirectional"))
      (node (ref "U1") (pin "34") (pinfunction "VCC_34") (pintype "bidirectional"))
      (node (ref "U1") (pin "44") (pinfunction "AVCC_44") (pintype "bidirectional"))
      (node (ref "U1") (pin "7") (pinfunction "VBUS_7") (pintype "bidirectional"))
    )
  )
)
